# Sheet5_PowerSupply_Connecters.net
KiCad netlist of a schematic drawn in Altium Designer
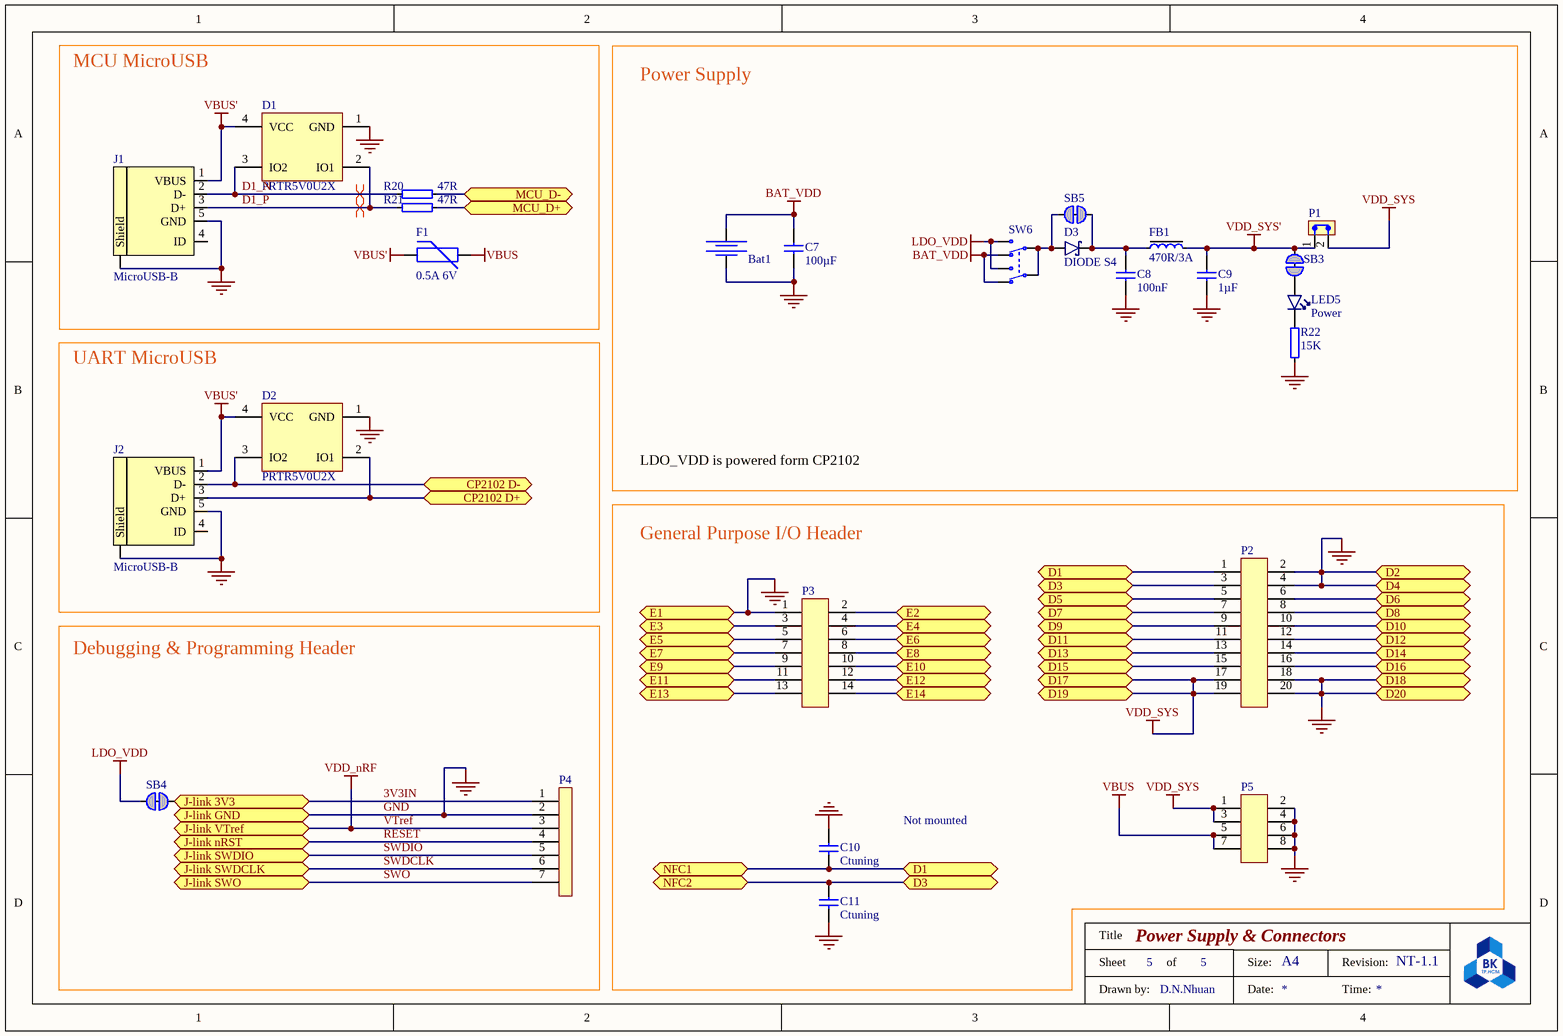
[diagram p0: Sheet5_PowerSupply&Connecters.SchDoc]

(export (version "E")
  (design (tool "Eeschema 10.0.6"))
  (components
    (comp (ref "Bat1")
      (value "Bat Holder CR2032")
      (footprint "CR2032_HOLDER")
      (description "Bat Holder CR2032 SMD")
      (libsource (lib "Project_Library") (part "Bat Holder CR2032"))
    )
    (comp (ref "C7")
      (value "100µF")
      (footprint "1210_Imperial")
      (description "Genaral Schematic")
      (fields (field (name "TOLERANCE") "±5%"))
      (libsource (lib "Project_Library") (part "Capacitor"))
    )
    (comp (ref "C8")
      (value "100nF")
      (footprint "0402 imperial")
      (description "Genaral Schematic")
      (fields (field (name "TOLERANCE") "±5%"))
      (libsource (lib "Project_Library") (part "Capacitor"))
    )
    (comp (ref "C9")
      (value "1µF")
      (footprint "0603_Imperial")
      (description "Genaral Schematic")
      (fields (field (name "TOLERANCE") "±5%"))
      (libsource (lib "Project_Library") (part "Capacitor"))
    )
    (comp (ref "C10")
      (value "Ctuning")
      (footprint "0402 imperial")
      (description "Genaral Schematic")
      (fields (field (name "TOLERANCE") "±5%"))
      (libsource (lib "Project_Library") (part "Capacitor"))
    )
    (comp (ref "C11")
      (value "Ctuning")
      (footprint "0402 imperial")
      (description "Genaral Schematic")
      (fields (field (name "TOLERANCE") "±5%"))
      (libsource (lib "Project_Library") (part "Capacitor"))
    )
    (comp (ref "D1")
      (value "PRTR5V0U2X")
      (footprint "SOT190P230X110-4L")
      (description "Ultra low capacitance double rail-to-rail ESD protection diode")
      (fields
        (field (name "MANUFACTURER") "NXP")
        (field (name "2ND SOURCE PART NUMBER") "152-4157")
        (field (name "PUBLISHER") "Nordic Semiconductor")
      )
      (libsource (lib "pca10056") (part "PRTR5V0U2X"))
    )
    (comp (ref "D2")
      (value "PRTR5V0U2X")
      (footprint "SOT190P230X110-4L")
      (description "Ultra low capacitance double rail-to-rail ESD protection diode")
      (fields
        (field (name "MANUFACTURER") "NXP")
        (field (name "2ND SOURCE PART NUMBER") "152-4157")
        (field (name "PUBLISHER") "Nordic Semiconductor")
      )
      (libsource (lib "pca10056") (part "PRTR5V0U2X"))
    )
    (comp (ref "D3")
      (value "DIODE S4")
      (footprint "SOD-123")
      (description "Diode Schottky")
      (libsource (lib "Project_Library") (part "Diode Schottky"))
    )
    (comp (ref "F1")
      (value "0.5A 6V")
      (footprint "0805_Imperial")
      (description "Fuse Fuse Fuse")
      (libsource (lib "Project_Library") (part "Fuse"))
    )
    (comp (ref "FB1")
      (value "470R/3A")
      (footprint "0603_Imperial")
      (description "General FB")
      (libsource (lib "Project_Library") (part "Ferrite Bead"))
    )
    (comp (ref "J1")
      (value "MicroUSB-B")
      (footprint "USB-Micro-B-RA-SMD-PiP")
      (description "MicroUSB-B-SMT")
      (fields
        (field (name "PART NUMBER") "USB-Micro-B-RA-SMD-PiP")
        (field (name "MANUFACTURER") "Allen Creations Corp.")
        (field (name "PUBLISHER") "Nordic Semiconductor")
      )
      (libsource (lib "pca10056") (part "MiniUSB-AB-SMT"))
    )
    (comp (ref "J2")
      (value "MicroUSB-B")
      (footprint "USB-Micro-B-RA-SMD-PiP")
      (description "MicroUSB-B-SMT")
      (fields
        (field (name "PART NUMBER") "USB-Micro-B-RA-SMD-PiP")
        (field (name "MANUFACTURER") "Allen Creations Corp.")
        (field (name "PUBLISHER") "Nordic Semiconductor")
      )
      (libsource (lib "pca10056") (part "MiniUSB-AB-SMT"))
    )
    (comp (ref "LED5")
      (value "Power")
      (footprint "LED_0603")
      (description "General Schematic")
      (libsource (lib "Project_Library") (part "LED"))
    )
    (comp (ref "P1")
      (value "2p, 2.54mm")
      (footprint "CONN2.54MM2P")
      (libsource (lib "Project_Library") (part "Headerx 2"))
    )
    (comp (ref "P2")
      (value "10x2, 2.54mm")
      (footprint "CONN2.54MM10X2")
      (description "General Schematic")
      (libsource (lib "Project_Library") (part "Header 10x2"))
    )
    (comp (ref "P3")
      (value "2x7p, 2.54mm")
      (footprint "CONN2.54MM7PX2")
      (description "General Schematic")
      (libsource (lib "Project_Library") (part "Header 7x2"))
    )
    (comp (ref "P4")
      (value "Debug&Programming")
      (footprint "CONN2.54MM7P")
      (description "General Schematic")
      (libsource (lib "Project_library") (part "Header 7"))
    )
    (comp (ref "P5")
      (value "2x4p, 2.54mm")
      (footprint "CONN2.54MM2X4")
      (description "General Schematic")
      (libsource (lib "Project_Library") (part "Header 4x2"))
    )
    (comp (ref "R20")
      (value "47R")
      (footprint "0402 imperial")
      (description "General Schematic")
      (fields (field (name "TOLERANCE") "±5%"))
      (libsource (lib "Project_Library") (part "Resistor"))
    )
    (comp (ref "R21")
      (value "47R")
      (footprint "0402 imperial")
      (description "General Schematic")
      (fields (field (name "TOLERANCE") "±5%"))
      (libsource (lib "Project_Library") (part "Resistor"))
    )
    (comp (ref "R22")
      (value "15K")
      (footprint "0402 imperial")
      (description "General Schematic")
      (fields (field (name "TOLERANCE") "±5%"))
      (libsource (lib "Project_Library") (part "Resistor"))
    )
    (comp (ref "SB3")
      (value "Solderbridge")
      (footprint "Solderbridge_Shorted")
      (description "Shorted Solderbridge")
      (fields
        (field (name "PART NUMBER") "Solderbridge Shorted")
        (field (name "PUBLISHER") "Nordic Semiconductor")
      )
      (libsource (lib "pca10056") (part "Solderbridge Shorted"))
    )
    (comp (ref "SB4")
      (value "Solderbridge")
      (footprint "Solderbridge_Shorted")
      (description "Shorted Solderbridge")
      (fields
        (field (name "PART NUMBER") "Solderbridge Shorted")
        (field (name "PUBLISHER") "Nordic Semiconductor")
      )
      (libsource (lib "pca10056") (part "Solderbridge Shorted"))
    )
    (comp (ref "SB5")
      (value "Solderbridge")
      (footprint "Solderbridge_Shorted")
      (description "Shorted Solderbridge")
      (fields
        (field (name "PART NUMBER") "Solderbridge Shorted")
        (field (name "PUBLISHER") "Nordic Semiconductor")
      )
      (libsource (lib "pca10056") (part "Solderbridge Shorted"))
    )
    (comp (ref "SW6")
      (value "MSS22D18")
      (footprint "MSS22D18SMD")
      (description "Slide Switch DPDT")
      (libsource (lib "Project_Library") (part "MSS22D18"))
    )
  )
  (nets
    (net (code "1") (name "/3V3IN") (class "Default")
      (node (ref "P4") (pin "1") (pinfunction "1_1") (pintype "passive"))
      (node (ref "SB4") (pin "2") (pinfunction "1_2") (pintype "passive"))
    )
    (net (code "2") (name "/CP2102 D+") (class "Default")
      (node (ref "D2") (pin "2") (pinfunction "IO1_2") (pintype "passive"))
      (node (ref "J2") (pin "3") (pinfunction "D+_3") (pintype "passive"))
    )
    (net (code "3") (name "/CP2102 D-") (class "Default")
      (node (ref "D2") (pin "3") (pinfunction "IO2_3") (pintype "passive"))
      (node (ref "J2") (pin "2") (pinfunction "D-_2") (pintype "passive"))
    )
    (net (code "4") (name "/D1") (class "Default")
      (node (ref "C10") (pin "1") (pinfunction "1_1") (pintype "passive"))
      (node (ref "P2") (pin "1") (pintype "passive"))
    )
    (net (code "5") (name "/D1_N") (class "Default")
      (node (ref "D1") (pin "3") (pinfunction "IO2_3") (pintype "passive"))
      (node (ref "J1") (pin "2") (pinfunction "D-_2") (pintype "passive"))
      (node (ref "R20") (pin "1") (pinfunction "1_1") (pintype "passive"))
    )
    (net (code "6") (name "/D1_P") (class "Default")
      (node (ref "D1") (pin "2") (pinfunction "IO1_2") (pintype "passive"))
      (node (ref "J1") (pin "3") (pinfunction "D+_3") (pintype "passive"))
      (node (ref "R21") (pin "1") (pinfunction "1_1") (pintype "passive"))
    )
    (net (code "7") (name "/D3") (class "Default")
      (node (ref "C11") (pin "2") (pinfunction "2_2") (pintype "passive"))
      (node (ref "P2") (pin "3") (pintype "passive"))
    )
    (net (code "8") (name "/D5") (class "Default") (node (ref "P2") (pin "5") (pintype "passive")))
    (net (code "9") (name "/D6") (class "Default") (node (ref "P2") (pin "6") (pintype "passive")))
    (net (code "10") (name "/D7") (class "Default") (node (ref "P2") (pin "7") (pintype "passive")))
    (net (code "11") (name "/D8") (class "Default") (node (ref "P2") (pin "8") (pintype "passive")))
    (net (code "12") (name "/D9") (class "Default") (node (ref "P2") (pin "9") (pintype "passive")))
    (net (code "13") (name "/D10") (class "Default") (node (ref "P2") (pin "10") (pintype "passive")))
    (net (code "14") (name "/D11") (class "Default") (node (ref "P2") (pin "11") (pintype "passive")))
    (net (code "15") (name "/D12") (class "Default") (node (ref "P2") (pin "12") (pintype "passive")))
    (net (code "16") (name "/D13") (class "Default") (node (ref "P2") (pin "13") (pintype "passive")))
    (net (code "17") (name "/D14") (class "Default") (node (ref "P2") (pin "14") (pintype "passive")))
    (net (code "18") (name "/D15") (class "Default") (node (ref "P2") (pin "15") (pintype "passive")))
    (net (code "19") (name "/D16") (class "Default") (node (ref "P2") (pin "16") (pintype "passive")))
    (net (code "20") (name "/E2") (class "Default")
      (node (ref "P3") (pin "2") (pinfunction "2_2") (pintype "passive"))
    )
    (net (code "21") (name "/E3") (class "Default")
      (node (ref "P3") (pin "3") (pinfunction "3_3") (pintype "passive"))
    )
    (net (code "22") (name "/E4") (class "Default")
      (node (ref "P3") (pin "4") (pinfunction "4_4") (pintype "passive"))
    )
    (net (code "23") (name "/E5") (class "Default")
      (node (ref "P3") (pin "5") (pinfunction "5_5") (pintype "passive"))
    )
    (net (code "24") (name "/E6") (class "Default")
      (node (ref "P3") (pin "6") (pinfunction "6_6") (pintype "passive"))
    )
    (net (code "25") (name "/E7") (class "Default")
      (node (ref "P3") (pin "7") (pinfunction "7_7") (pintype "passive"))
    )
    (net (code "26") (name "/E8") (class "Default")
      (node (ref "P3") (pin "8") (pinfunction "8_8") (pintype "passive"))
    )
    (net (code "27") (name "/E9") (class "Default")
      (node (ref "P3") (pin "9") (pinfunction "9_9") (pintype "passive"))
    )
    (net (code "28") (name "/E10") (class "Default")
      (node (ref "P3") (pin "10") (pinfunction "10_10") (pintype "passive"))
    )
    (net (code "29") (name "/E11") (class "Default")
      (node (ref "P3") (pin "11") (pinfunction "11_11") (pintype "passive"))
    )
    (net (code "30") (name "/E12") (class "Default")
      (node (ref "P3") (pin "12") (pinfunction "12_12") (pintype "passive"))
    )
    (net (code "31") (name "/E13") (class "Default")
      (node (ref "P3") (pin "13") (pinfunction "13_13") (pintype "passive"))
    )
    (net (code "32") (name "/E14") (class "Default")
      (node (ref "P3") (pin "14") (pinfunction "14_14") (pintype "passive"))
    )
    (net (code "33") (name "/MCU_D+") (class "Default")
      (node (ref "R21") (pin "2") (pinfunction "2_2") (pintype "passive"))
    )
    (net (code "34") (name "/MCU_D-") (class "Default")
      (node (ref "R20") (pin "2") (pinfunction "2_2") (pintype "passive"))
    )
    (net (code "35") (name "/RESET") (class "Default")
      (node (ref "P4") (pin "4") (pinfunction "4_4") (pintype "passive"))
    )
    (net (code "36") (name "/SWDCLK") (class "Default")
      (node (ref "P4") (pin "6") (pinfunction "6_6") (pintype "passive"))
    )
    (net (code "37") (name "/SWDIO") (class "Default")
      (node (ref "P4") (pin "5") (pinfunction "5_5") (pintype "passive"))
    )
    (net (code "38") (name "/SWO") (class "Default")
      (node (ref "P4") (pin "7") (pinfunction "7_7") (pintype "passive"))
    )
    (net (code "39") (name "BAT_VDD") (class "Default")
      (node (ref "Bat1") (pin "1") (pinfunction "1_1") (pintype "passive"))
      (node (ref "C7") (pin "2") (pinfunction "2_2") (pintype "passive"))
      (node (ref "SW6") (pin "3") (pinfunction "N.C-1_3") (pintype "passive"))
      (node (ref "SW6") (pin "6") (pinfunction "N.C-2_6") (pintype "passive"))
    )
    (net (code "40") (name "GND") (class "Default")
      (node (ref "Bat1") (pin "2") (pinfunction "2_2") (pintype "passive"))
      (node (ref "C10") (pin "2") (pinfunction "2_2") (pintype "passive"))
      (node (ref "C11") (pin "1") (pinfunction "1_1") (pintype "passive"))
      (node (ref "C7") (pin "1") (pinfunction "1_1") (pintype "passive"))
      (node (ref "C8") (pin "1") (pinfunction "1_1") (pintype "passive"))
      (node (ref "C9") (pin "1") (pinfunction "1_1") (pintype "passive"))
      (node (ref "D1") (pin "1") (pinfunction "GND_1") (pintype "passive"))
      (node (ref "D2") (pin "1") (pinfunction "GND_1") (pintype "passive"))
      (node (ref "J1") (pin "5") (pinfunction "GND_5") (pintype "power_in"))
      (node (ref "J1") (pin "6") (pinfunction "Shield_6") (pintype "power_in"))
      (node (ref "J2") (pin "5") (pinfunction "GND_5") (pintype "power_in"))
      (node (ref "J2") (pin "6") (pinfunction "Shield_6") (pintype "power_in"))
      (node (ref "P2") (pin "18") (pintype "passive"))
      (node (ref "P2") (pin "2") (pintype "passive"))
      (node (ref "P2") (pin "20") (pintype "passive"))
      (node (ref "P2") (pin "4") (pintype "passive"))
      (node (ref "P3") (pin "1") (pinfunction "1_1") (pintype "passive"))
      (node (ref "P4") (pin "2") (pinfunction "2_2") (pintype "passive"))
      (node (ref "P5") (pin "2") (pinfunction "2_2") (pintype "passive"))
      (node (ref "P5") (pin "4") (pinfunction "4_4") (pintype "passive"))
      (node (ref "P5") (pin "6") (pinfunction "6_6") (pintype "passive"))
      (node (ref "P5") (pin "8") (pinfunction "8_8") (pintype "passive"))
      (node (ref "R22") (pin "1") (pinfunction "1_1") (pintype "passive"))
    )
    (net (code "41") (name "LDO_VDD") (class "Default")
      (node (ref "SB4") (pin "1") (pinfunction "0_1") (pintype "passive"))
      (node (ref "SW6") (pin "1") (pinfunction "N.O-1_1") (pintype "passive"))
      (node (ref "SW6") (pin "4") (pinfunction "N.O-2_4") (pintype "passive"))
    )
    (net (code "42") (name "Net-(D3-A)") (class "Default")
      (node (ref "D3") (pin "2") (pinfunction "A_2") (pintype "passive"))
      (node (ref "SB5") (pin "2") (pinfunction "1_2") (pintype "passive"))
      (node (ref "SW6") (pin "2") (pinfunction "COM-1_2") (pintype "passive"))
      (node (ref "SW6") (pin "5") (pinfunction "COM-2_5") (pintype "passive"))
    )
    (net (code "43") (name "Net-(D3-C)") (class "Default")
      (node (ref "C8") (pin "2") (pinfunction "2_2") (pintype "passive"))
      (node (ref "D3") (pin "1") (pinfunction "C_1") (pintype "passive"))
      (node (ref "FB1") (pin "1") (pinfunction "1_1") (pintype "passive"))
      (node (ref "SB5") (pin "1") (pinfunction "0_1") (pintype "passive"))
    )
    (net (code "44") (name "Net-(LED5-A)") (class "Default")
      (node (ref "LED5") (pin "2") (pinfunction "A_2") (pintype "passive"))
      (node (ref "SB3") (pin "2") (pinfunction "1_2") (pintype "passive"))
    )
    (net (code "45") (name "Net-(LED5-C)") (class "Default")
      (node (ref "LED5") (pin "1") (pinfunction "C_1") (pintype "passive"))
      (node (ref "R22") (pin "2") (pinfunction "2_2") (pintype "passive"))
    )
    (net (code "46") (name "VBUS") (class "Default")
      (node (ref "F1") (pin "2") (pinfunction "2_2") (pintype "passive"))
      (node (ref "P5") (pin "5") (pinfunction "5_5") (pintype "passive"))
      (node (ref "P5") (pin "7") (pinfunction "7_7") (pintype "passive"))
    )
    (net (code "47") (name "VBUS'") (class "Default")
      (node (ref "D1") (pin "4") (pinfunction "VCC_4") (pintype "passive"))
      (node (ref "D2") (pin "4") (pinfunction "VCC_4") (pintype "passive"))
      (node (ref "F1") (pin "1") (pinfunction "1_1") (pintype "passive"))
      (node (ref "J1") (pin "1") (pinfunction "VBUS_1") (pintype "power_in"))
      (node (ref "J2") (pin "1") (pinfunction "VBUS_1") (pintype "power_in"))
    )
    (net (code "48") (name "VDD_SYS") (class "Default")
      (node (ref "P1") (pin "2") (pinfunction "2_2") (pintype "passive"))
      (node (ref "P2") (pin "17") (pintype "passive"))
      (node (ref "P2") (pin "19") (pintype "passive"))
      (node (ref "P5") (pin "1") (pinfunction "1_1") (pintype "passive"))
      (node (ref "P5") (pin "3") (pinfunction "3_3") (pintype "passive"))
    )
    (net (code "49") (name "VDD_SYS'") (class "Default")
      (node (ref "C9") (pin "2") (pinfunction "2_2") (pintype "passive"))
      (node (ref "FB1") (pin "2") (pinfunction "2_2") (pintype "passive"))
      (node (ref "P1") (pin "1") (pinfunction "1_1") (pintype "passive"))
      (node (ref "SB3") (pin "1") (pinfunction "0_1") (pintype "passive"))
    )
    (net (code "50") (name "VDD_nRF") (class "Default")
      (node (ref "P4") (pin "3") (pinfunction "3_3") (pintype "passive"))
    )
    (net (code "51") (name "unconnected-(J1-ID-Pad4)") (class "Default")
      (node (ref "J1") (pin "4") (pinfunction "ID_4") (pintype "passive"))
    )
    (net (code "52") (name "unconnected-(J2-ID-Pad4)") (class "Default")
      (node (ref "J2") (pin "4") (pinfunction "ID_4") (pintype "passive"))
    )
  )
)
